# Bottom_PCB_v36.net
KiCad netlist of a schematic drawn in EAGLE
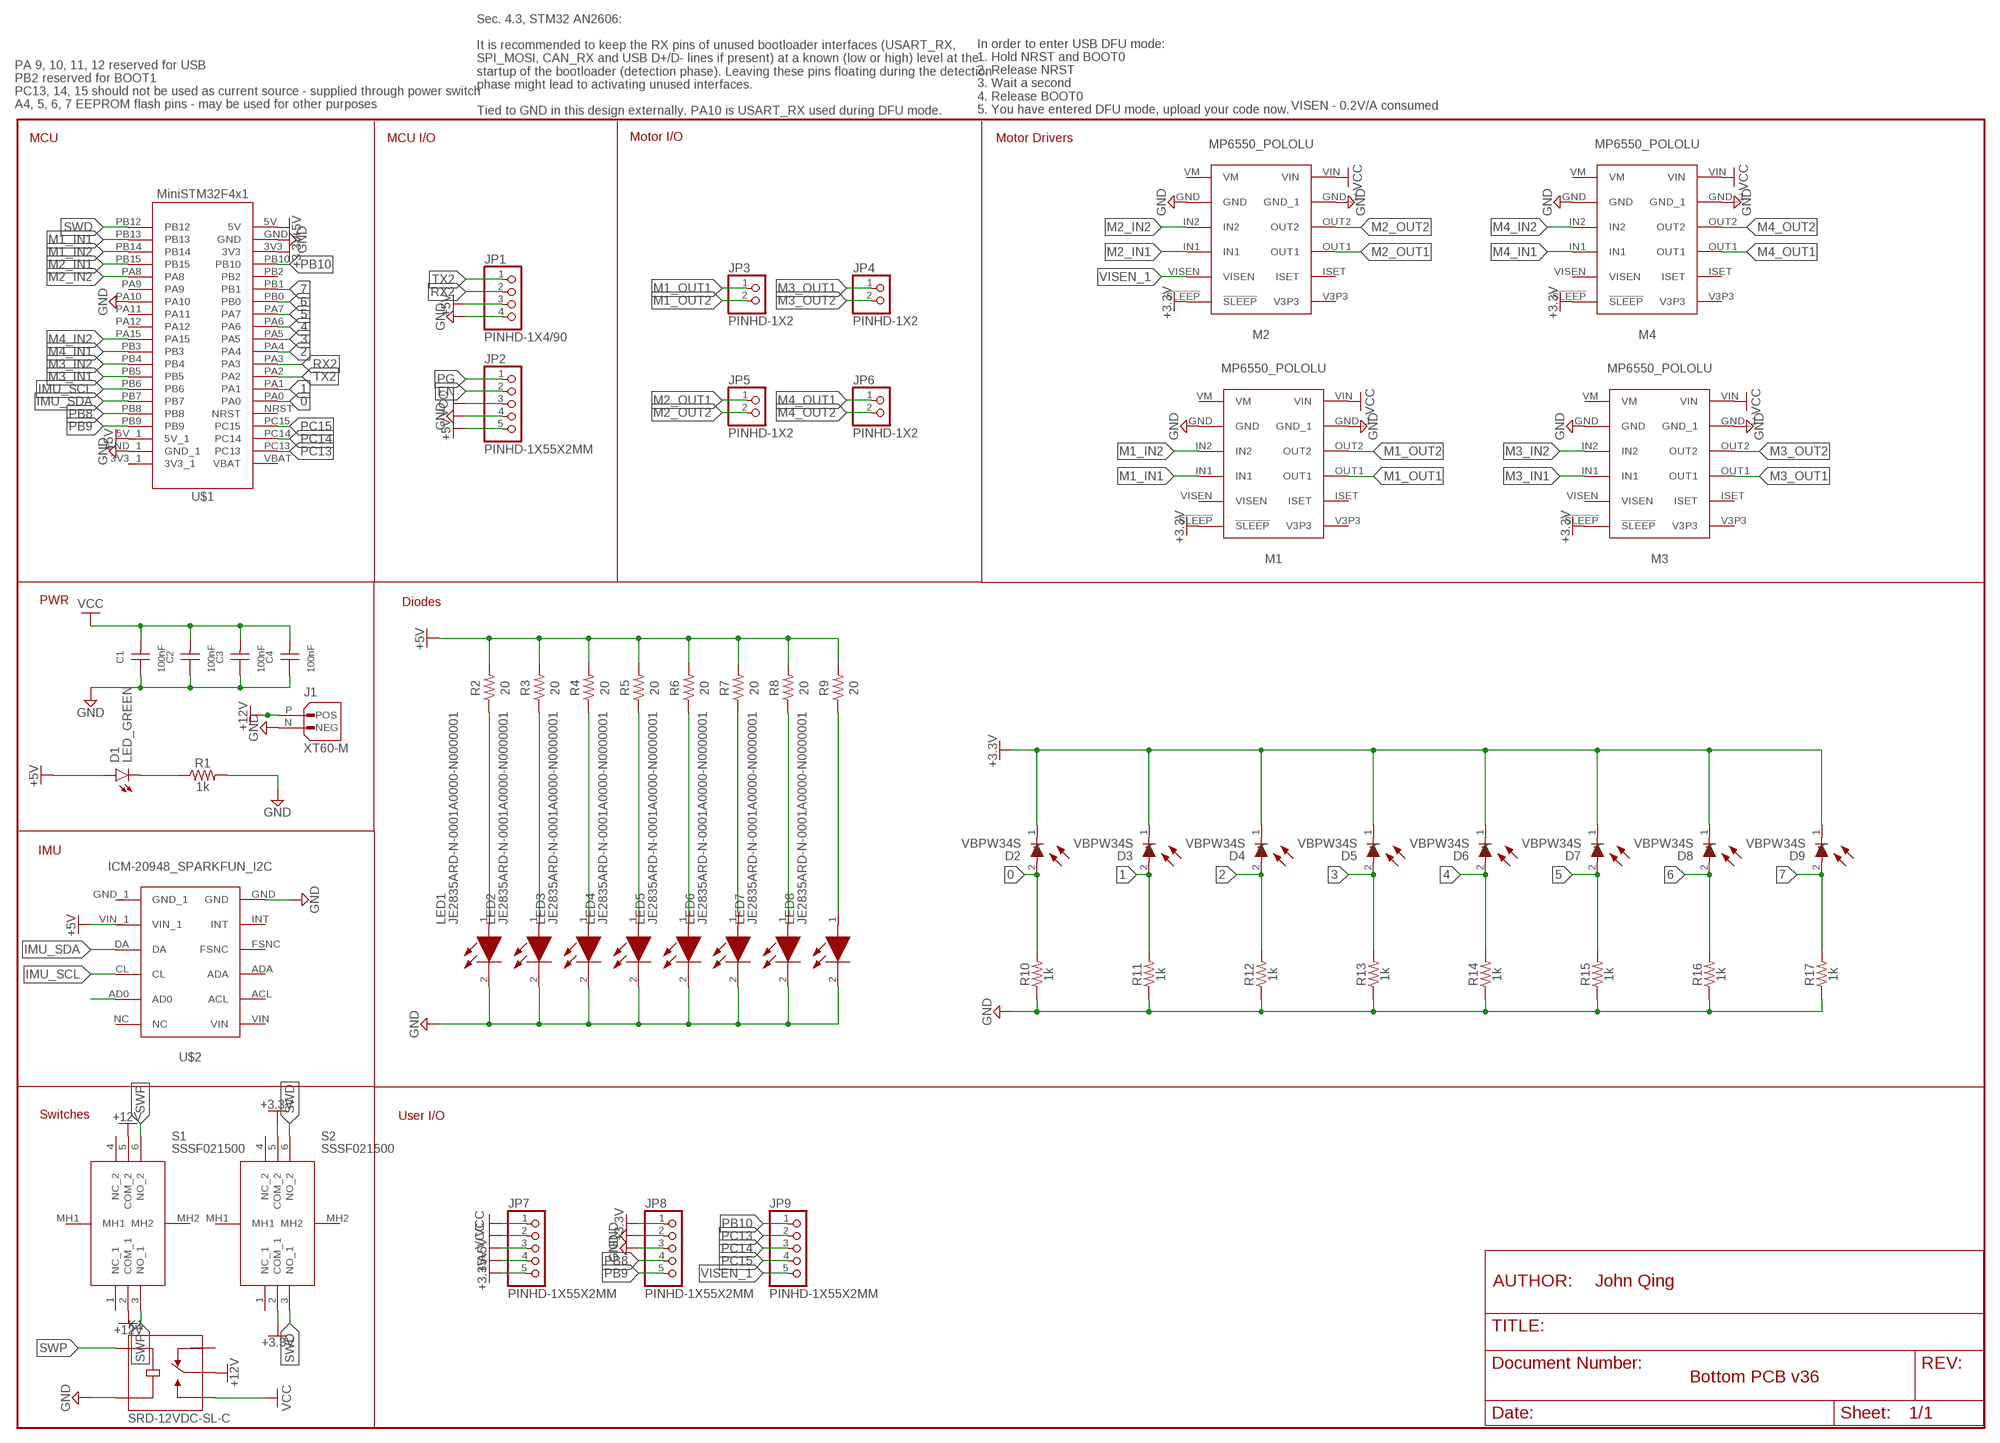
[diagram p0: schematic, sheet 1]

(export (version "E")
  (design (tool "Eeschema 10.0.6"))
  (components
    (comp (ref "C1")
      (value "100nF")
      (footprint "eagle-import:WCAP-CSGP_0603_W")
      (libsource (lib "eagle-import") (part "WCAP-CSGP_0603_100V(DC)_W_885012206120"))
    )
    (comp (ref "C2")
      (value "100nF")
      (footprint "eagle-import:WCAP-CSGP_0603_W")
      (libsource (lib "eagle-import") (part "WCAP-CSGP_0603_100V(DC)_W_885012206120"))
    )
    (comp (ref "C3")
      (value "100nF")
      (footprint "eagle-import:WCAP-CSGP_0603_W")
      (libsource (lib "eagle-import") (part "WCAP-CSGP_0603_100V(DC)_W_885012206120"))
    )
    (comp (ref "C4")
      (value "100nF")
      (footprint "eagle-import:WCAP-CSGP_0603_W")
      (libsource (lib "eagle-import") (part "WCAP-CSGP_0603_100V(DC)_W_885012206120"))
    )
    (comp (ref "D1")
      (value "LED_GREEN")
      (footprint "eagle-import:LEDC1005X25N_FLAT-G")
      (libsource (lib "eagle-import") (part "CHIP-FLAT-G_0402"))
    )
    (comp (ref "D2")
      (value "VBPW34S")
      (footprint "eagle-import:VBPW34S")
      (fields (field (name "MOUSER_PART_NUMBER") "782-VBPW34S"))
      (libsource (lib "eagle-import") (part "VBPW34S"))
    )
    (comp (ref "D3")
      (value "VBPW34S")
      (footprint "eagle-import:VBPW34S")
      (fields (field (name "MOUSER_PART_NUMBER") "782-VBPW34S"))
      (libsource (lib "eagle-import") (part "VBPW34S"))
    )
    (comp (ref "D4")
      (value "VBPW34S")
      (footprint "eagle-import:VBPW34S")
      (fields (field (name "MOUSER_PART_NUMBER") "782-VBPW34S"))
      (libsource (lib "eagle-import") (part "VBPW34S"))
    )
    (comp (ref "D5")
      (value "VBPW34S")
      (footprint "eagle-import:VBPW34S")
      (fields (field (name "MOUSER_PART_NUMBER") "782-VBPW34S"))
      (libsource (lib "eagle-import") (part "VBPW34S"))
    )
    (comp (ref "D6")
      (value "VBPW34S")
      (footprint "eagle-import:VBPW34S")
      (fields (field (name "MOUSER_PART_NUMBER") "782-VBPW34S"))
      (libsource (lib "eagle-import") (part "VBPW34S"))
    )
    (comp (ref "D7")
      (value "VBPW34S")
      (footprint "eagle-import:VBPW34S")
      (fields (field (name "MOUSER_PART_NUMBER") "782-VBPW34S"))
      (libsource (lib "eagle-import") (part "VBPW34S"))
    )
    (comp (ref "D8")
      (value "VBPW34S")
      (footprint "eagle-import:VBPW34S")
      (fields (field (name "MOUSER_PART_NUMBER") "782-VBPW34S"))
      (libsource (lib "eagle-import") (part "VBPW34S"))
    )
    (comp (ref "D9")
      (value "VBPW34S")
      (footprint "eagle-import:VBPW34S")
      (fields (field (name "MOUSER_PART_NUMBER") "782-VBPW34S"))
      (libsource (lib "eagle-import") (part "VBPW34S"))
    )
    (comp (ref "J1")
      (value "XT60-M")
      (footprint "eagle-import:AMASS_XT60-M")
      (fields (field (name "MF") "AMASS"))
      (libsource (lib "eagle-import") (part "XT60-M"))
    )
    (comp (ref "JP1")
      (value "PINHD-1X4/90")
      (footprint "eagle-import:1X04_90")
      (fields (field (name "MANUFACTURER") "Generic"))
      (libsource (lib "eagle-import") (part "PINHD-1X4/90"))
    )
    (comp (ref "JP2")
      (value "PINHD-1X55X2MM")
      (footprint "eagle-import:1_05X2MM")
      (fields (field (name "MANUFACTURER") "Generic"))
      (libsource (lib "eagle-import") (part "PINHD-1X55X2MM"))
    )
    (comp (ref "JP3")
      (value "PINHD-1X2")
      (footprint "eagle-import:1X02")
      (fields (field (name "MANUFACTURER") "Generic"))
      (libsource (lib "eagle-import") (part "PINHD-1X2"))
    )
    (comp (ref "JP4")
      (value "PINHD-1X2")
      (footprint "eagle-import:1X02")
      (fields (field (name "MANUFACTURER") "Generic"))
      (libsource (lib "eagle-import") (part "PINHD-1X2"))
    )
    (comp (ref "JP5")
      (value "PINHD-1X2")
      (footprint "eagle-import:1X02")
      (fields (field (name "MANUFACTURER") "Generic"))
      (libsource (lib "eagle-import") (part "PINHD-1X2"))
    )
    (comp (ref "JP6")
      (value "PINHD-1X2")
      (footprint "eagle-import:1X02")
      (fields (field (name "MANUFACTURER") "Generic"))
      (libsource (lib "eagle-import") (part "PINHD-1X2"))
    )
    (comp (ref "JP7")
      (value "PINHD-1X55X2MM")
      (footprint "eagle-import:1_05X2MM")
      (fields (field (name "MANUFACTURER") "Generic"))
      (libsource (lib "eagle-import") (part "PINHD-1X55X2MM"))
    )
    (comp (ref "JP8")
      (value "PINHD-1X55X2MM")
      (footprint "eagle-import:1_05X2MM")
      (fields (field (name "MANUFACTURER") "Generic"))
      (libsource (lib "eagle-import") (part "PINHD-1X55X2MM"))
    )
    (comp (ref "JP9")
      (value "PINHD-1X55X2MM")
      (footprint "eagle-import:1_05X2MM")
      (fields (field (name "MANUFACTURER") "Generic"))
      (libsource (lib "eagle-import") (part "PINHD-1X55X2MM"))
    )
    (comp (ref "K1")
      (value "SRD-12VDC-SL-C")
      (footprint "eagle-import:RELAY_SRD-12VDC-SL-C")
      (fields (field (name "MF") "Songle Relay"))
      (libsource (lib "eagle-import") (part "SRD-12VDC-SL-C"))
    )
    (comp (ref "LED1")
      (value "JE2835ARD-N-0001A0000-N0000001")
      (footprint "eagle-import:JE2835ARDN0001A0000N0000001")
      (fields (field (name "MOUSER_PART_NUMBER") "941-JE2835ARDN01AN"))
      (libsource (lib "eagle-import") (part "JE2835ARD-N-0001A0000-N0000001"))
    )
    (comp (ref "LED2")
      (value "JE2835ARD-N-0001A0000-N0000001")
      (footprint "eagle-import:JE2835ARDN0001A0000N0000001")
      (fields (field (name "MOUSER_PART_NUMBER") "941-JE2835ARDN01AN"))
      (libsource (lib "eagle-import") (part "JE2835ARD-N-0001A0000-N0000001"))
    )
    (comp (ref "LED3")
      (value "JE2835ARD-N-0001A0000-N0000001")
      (footprint "eagle-import:JE2835ARDN0001A0000N0000001")
      (fields (field (name "MOUSER_PART_NUMBER") "941-JE2835ARDN01AN"))
      (libsource (lib "eagle-import") (part "JE2835ARD-N-0001A0000-N0000001"))
    )
    (comp (ref "LED4")
      (value "JE2835ARD-N-0001A0000-N0000001")
      (footprint "eagle-import:JE2835ARDN0001A0000N0000001")
      (fields (field (name "MOUSER_PART_NUMBER") "941-JE2835ARDN01AN"))
      (libsource (lib "eagle-import") (part "JE2835ARD-N-0001A0000-N0000001"))
    )
    (comp (ref "LED5")
      (value "JE2835ARD-N-0001A0000-N0000001")
      (footprint "eagle-import:JE2835ARDN0001A0000N0000001")
      (fields (field (name "MOUSER_PART_NUMBER") "941-JE2835ARDN01AN"))
      (libsource (lib "eagle-import") (part "JE2835ARD-N-0001A0000-N0000001"))
    )
    (comp (ref "LED6")
      (value "JE2835ARD-N-0001A0000-N0000001")
      (footprint "eagle-import:JE2835ARDN0001A0000N0000001")
      (fields (field (name "MOUSER_PART_NUMBER") "941-JE2835ARDN01AN"))
      (libsource (lib "eagle-import") (part "JE2835ARD-N-0001A0000-N0000001"))
    )
    (comp (ref "LED7")
      (value "JE2835ARD-N-0001A0000-N0000001")
      (footprint "eagle-import:JE2835ARDN0001A0000N0000001")
      (fields (field (name "MOUSER_PART_NUMBER") "941-JE2835ARDN01AN"))
      (libsource (lib "eagle-import") (part "JE2835ARD-N-0001A0000-N0000001"))
    )
    (comp (ref "LED8")
      (value "JE2835ARD-N-0001A0000-N0000001")
      (footprint "eagle-import:JE2835ARDN0001A0000N0000001")
      (fields (field (name "MOUSER_PART_NUMBER") "941-JE2835ARDN01AN"))
      (libsource (lib "eagle-import") (part "JE2835ARD-N-0001A0000-N0000001"))
    )
    (comp (ref "M1")
      (value "MP6550_POLOLU")
      (footprint "eagle-import:MP6550_POLOLU")
      (libsource (lib "eagle-import") (part "MP6550_POLOLU"))
    )
    (comp (ref "M2")
      (value "MP6550_POLOLU")
      (footprint "eagle-import:MP6550_POLOLU")
      (libsource (lib "eagle-import") (part "MP6550_POLOLU"))
    )
    (comp (ref "M3")
      (value "MP6550_POLOLU")
      (footprint "eagle-import:MP6550_POLOLU")
      (libsource (lib "eagle-import") (part "MP6550_POLOLU"))
    )
    (comp (ref "M4")
      (value "MP6550_POLOLU")
      (footprint "eagle-import:MP6550_POLOLU")
      (libsource (lib "eagle-import") (part "MP6550_POLOLU"))
    )
    (comp (ref "R1")
      (value "1k")
      (footprint "eagle-import:0603")
      (libsource (lib "eagle-import") (part "1KOHM-0603-1/10W-1%"))
    )
    (comp (ref "R2")
      (value "20")
      (footprint "eagle-import:RESC3224X71")
      (libsource (lib "eagle-import") (part "R-USCHIP-1210(3225-METRIC)_"))
    )
    (comp (ref "R3")
      (value "20")
      (footprint "eagle-import:RESC3224X71")
      (libsource (lib "eagle-import") (part "R-USCHIP-1210(3225-METRIC)_"))
    )
    (comp (ref "R4")
      (value "20")
      (footprint "eagle-import:RESC3224X71")
      (libsource (lib "eagle-import") (part "R-USCHIP-1210(3225-METRIC)_"))
    )
    (comp (ref "R5")
      (value "20")
      (footprint "eagle-import:RESC3224X71")
      (libsource (lib "eagle-import") (part "R-USCHIP-1210(3225-METRIC)_"))
    )
    (comp (ref "R6")
      (value "20")
      (footprint "eagle-import:RESC3224X71")
      (libsource (lib "eagle-import") (part "R-USCHIP-1210(3225-METRIC)_"))
    )
    (comp (ref "R7")
      (value "20")
      (footprint "eagle-import:RESC3224X71")
      (libsource (lib "eagle-import") (part "R-USCHIP-1210(3225-METRIC)_"))
    )
    (comp (ref "R8")
      (value "20")
      (footprint "eagle-import:RESC3224X71")
      (libsource (lib "eagle-import") (part "R-USCHIP-1210(3225-METRIC)_"))
    )
    (comp (ref "R9")
      (value "20")
      (footprint "eagle-import:RESC3224X71")
      (libsource (lib "eagle-import") (part "R-USCHIP-1210(3225-METRIC)_"))
    )
    (comp (ref "R10")
      (value "1k")
      (footprint "eagle-import:0603")
      (libsource (lib "eagle-import") (part "1KOHM-0603-1/10W-1%"))
    )
    (comp (ref "R11")
      (value "1k")
      (footprint "eagle-import:0603")
      (libsource (lib "eagle-import") (part "1KOHM-0603-1/10W-1%"))
    )
    (comp (ref "R12")
      (value "1k")
      (footprint "eagle-import:0603")
      (libsource (lib "eagle-import") (part "1KOHM-0603-1/10W-1%"))
    )
    (comp (ref "R13")
      (value "1k")
      (footprint "eagle-import:0603")
      (libsource (lib "eagle-import") (part "1KOHM-0603-1/10W-1%"))
    )
    (comp (ref "R14")
      (value "1k")
      (footprint "eagle-import:0603")
      (libsource (lib "eagle-import") (part "1KOHM-0603-1/10W-1%"))
    )
    (comp (ref "R15")
      (value "1k")
      (footprint "eagle-import:0603")
      (libsource (lib "eagle-import") (part "1KOHM-0603-1/10W-1%"))
    )
    (comp (ref "R16")
      (value "1k")
      (footprint "eagle-import:0603")
      (libsource (lib "eagle-import") (part "1KOHM-0603-1/10W-1%"))
    )
    (comp (ref "R17")
      (value "1k")
      (footprint "eagle-import:0603")
      (libsource (lib "eagle-import") (part "1KOHM-0603-1/10W-1%"))
    )
    (comp (ref "S1")
      (value "SSSF021500")
      (footprint "eagle-import:SSSF021500")
      (fields (field (name "MOUSER_PART_NUMBER") "688-SSSF021500"))
      (libsource (lib "eagle-import") (part "SSSF021500"))
    )
    (comp (ref "S2")
      (value "SSSF021500")
      (footprint "eagle-import:SSSF021500")
      (fields (field (name "MOUSER_PART_NUMBER") "688-SSSF021500"))
      (libsource (lib "eagle-import") (part "SSSF021500"))
    )
    (comp (ref "U$1")
      (value "MINISTM32F4X1")
      (footprint "eagle-import:MINISTM32F4X1")
      (libsource (lib "eagle-import") (part "MINISTM32F4X1"))
    )
    (comp (ref "U$2")
      (value "ICM-20948_SPARKFUN_I2C")
      (footprint "eagle-import:ICM-20948_SPARKFUN_I2C")
      (libsource (lib "eagle-import") (part "ICM-20948_SPARKFUN_I2C"))
    )
  )
  (nets
    (net (code "1") (name "+3.3V") (class "Default")
      (node (ref "D2") (pin "1") (pinfunction "K_1") (pintype "bidirectional"))
      (node (ref "D3") (pin "1") (pinfunction "K_1") (pintype "bidirectional"))
      (node (ref "D4") (pin "1") (pinfunction "K_1") (pintype "bidirectional"))
      (node (ref "D5") (pin "1") (pinfunction "K_1") (pintype "bidirectional"))
      (node (ref "D6") (pin "1") (pinfunction "K_1") (pintype "bidirectional"))
      (node (ref "D7") (pin "1") (pinfunction "K_1") (pintype "bidirectional"))
      (node (ref "D8") (pin "1") (pinfunction "K_1") (pintype "bidirectional"))
      (node (ref "D9") (pin "1") (pinfunction "K_1") (pintype "bidirectional"))
      (node (ref "JP7") (pin "5") (pinfunction "5_5") (pintype "passive"))
      (node (ref "JP8") (pin "1") (pinfunction "1_1") (pintype "passive"))
      (node (ref "M1") (pin "!SLEEP") (pinfunction "~{SLEEP}_!SLEEP") (pintype "bidirectional"))
      (node (ref "M2") (pin "!SLEEP") (pinfunction "~{SLEEP}_!SLEEP") (pintype "bidirectional"))
      (node (ref "M3") (pin "!SLEEP") (pinfunction "~{SLEEP}_!SLEEP") (pintype "bidirectional"))
      (node (ref "M4") (pin "!SLEEP") (pinfunction "~{SLEEP}_!SLEEP") (pintype "bidirectional"))
      (node (ref "S2") (pin "2") (pinfunction "COM_1_2") (pintype "bidirectional"))
      (node (ref "S2") (pin "5") (pinfunction "COM_2_5") (pintype "bidirectional"))
      (node (ref "U$1") (pin "3V3") (pinfunction "3V3_3V3") (pintype "power_in"))
    )
    (net (code "2") (name "+5V") (class "Default")
      (node (ref "D1") (pin "A") (pinfunction "A_A") (pintype "passive"))
      (node (ref "JP1") (pin "3") (pinfunction "3_3") (pintype "passive"))
      (node (ref "JP2") (pin "5") (pinfunction "5_5") (pintype "passive"))
      (node (ref "JP7") (pin "3") (pinfunction "3_3") (pintype "passive"))
      (node (ref "JP7") (pin "4") (pinfunction "4_4") (pintype "passive"))
      (node (ref "R2") (pin "2") (pinfunction "2_2") (pintype "passive"))
      (node (ref "R3") (pin "2") (pinfunction "2_2") (pintype "passive"))
      (node (ref "R4") (pin "2") (pinfunction "2_2") (pintype "passive"))
      (node (ref "R5") (pin "2") (pinfunction "2_2") (pintype "passive"))
      (node (ref "R6") (pin "2") (pinfunction "2_2") (pintype "passive"))
      (node (ref "R7") (pin "2") (pinfunction "2_2") (pintype "passive"))
      (node (ref "R8") (pin "2") (pinfunction "2_2") (pintype "passive"))
      (node (ref "R9") (pin "2") (pinfunction "2_2") (pintype "passive"))
      (node (ref "U$1") (pin "5V") (pinfunction "5V_5V") (pintype "power_in"))
      (node (ref "U$1") (pin "5V_1") (pinfunction "5V_1_5V_1") (pintype "power_in"))
      (node (ref "U$2") (pin "VIN_1") (pinfunction "VIN_1_VIN_1") (pintype "bidirectional"))
    )
    (net (code "3") (name "+12V") (class "Default")
      (node (ref "J1") (pin "P") (pinfunction "POS_P") (pintype "passive"))
      (node (ref "K1") (pin "COM") (pinfunction "COM_COM") (pintype "passive"))
      (node (ref "S1") (pin "2") (pinfunction "COM_1_2") (pintype "bidirectional"))
      (node (ref "S1") (pin "5") (pinfunction "COM_2_5") (pintype "bidirectional"))
    )
    (net (code "4") (name "/3V3_1") (class "Default")
      (node (ref "U$1") (pin "3V3_1") (pinfunction "3V3_1_3V3_1") (pintype "power_in"))
    )
    (net (code "5") (name "0") (class "Default")
      (node (ref "D2") (pin "2") (pinfunction "A_2") (pintype "bidirectional"))
      (node (ref "R10") (pin "2") (pinfunction "2_2") (pintype "passive"))
      (node (ref "U$1") (pin "PA0") (pinfunction "PA0_PA0") (pintype "bidirectional"))
    )
    (net (code "6") (name "1") (class "Default")
      (node (ref "D3") (pin "2") (pinfunction "A_2") (pintype "bidirectional"))
      (node (ref "R11") (pin "2") (pinfunction "2_2") (pintype "passive"))
      (node (ref "U$1") (pin "PA1") (pinfunction "PA1_PA1") (pintype "bidirectional"))
    )
    (net (code "7") (name "2") (class "Default")
      (node (ref "D4") (pin "2") (pinfunction "A_2") (pintype "bidirectional"))
      (node (ref "R12") (pin "2") (pinfunction "2_2") (pintype "passive"))
      (node (ref "U$1") (pin "PA4") (pinfunction "PA4_PA4") (pintype "bidirectional"))
    )
    (net (code "8") (name "3") (class "Default")
      (node (ref "D5") (pin "2") (pinfunction "A_2") (pintype "bidirectional"))
      (node (ref "R13") (pin "2") (pinfunction "2_2") (pintype "passive"))
      (node (ref "U$1") (pin "PA5") (pinfunction "PA5_PA5") (pintype "bidirectional"))
    )
    (net (code "9") (name "4") (class "Default")
      (node (ref "D6") (pin "2") (pinfunction "A_2") (pintype "bidirectional"))
      (node (ref "R14") (pin "2") (pinfunction "2_2") (pintype "passive"))
      (node (ref "U$1") (pin "PA6") (pinfunction "PA6_PA6") (pintype "bidirectional"))
    )
    (net (code "10") (name "5") (class "Default")
      (node (ref "D7") (pin "2") (pinfunction "A_2") (pintype "bidirectional"))
      (node (ref "R15") (pin "2") (pinfunction "2_2") (pintype "passive"))
      (node (ref "U$1") (pin "PA7") (pinfunction "PA7_PA7") (pintype "bidirectional"))
    )
    (net (code "11") (name "6") (class "Default")
      (node (ref "D8") (pin "2") (pinfunction "A_2") (pintype "bidirectional"))
      (node (ref "R16") (pin "2") (pinfunction "2_2") (pintype "passive"))
      (node (ref "U$1") (pin "PB0") (pinfunction "PB0_PB0") (pintype "bidirectional"))
    )
    (net (code "12") (name "7") (class "Default")
      (node (ref "D9") (pin "2") (pinfunction "A_2") (pintype "bidirectional"))
      (node (ref "R17") (pin "2") (pinfunction "2_2") (pintype "passive"))
      (node (ref "U$1") (pin "PB1") (pinfunction "PB1_PB1") (pintype "bidirectional"))
    )
    (net (code "13") (name "EN") (class "Default")
      (node (ref "JP2") (pin "2") (pinfunction "2_2") (pintype "passive"))
    )
    (net (code "14") (name "GND") (class "Default")
      (node (ref "C1") (pin "1") (pinfunction "1_1") (pintype "passive"))
      (node (ref "C2") (pin "1") (pinfunction "1_1") (pintype "passive"))
      (node (ref "C3") (pin "1") (pinfunction "1_1") (pintype "passive"))
      (node (ref "C4") (pin "1") (pinfunction "1_1") (pintype "passive"))
      (node (ref "J1") (pin "N") (pinfunction "NEG_N") (pintype "passive"))
      (node (ref "JP1") (pin "4") (pinfunction "4_4") (pintype "passive"))
      (node (ref "JP2") (pin "4") (pinfunction "4_4") (pintype "passive"))
      (node (ref "JP8") (pin "2") (pinfunction "2_2") (pintype "passive"))
      (node (ref "JP8") (pin "3") (pinfunction "3_3") (pintype "passive"))
      (node (ref "K1") (pin "COIL2") (pinfunction "COIL2_COIL2") (pintype "passive"))
      (node (ref "LED1") (pin "2") (pinfunction "K_2") (pintype "bidirectional"))
      (node (ref "LED2") (pin "2") (pinfunction "K_2") (pintype "bidirectional"))
      (node (ref "LED3") (pin "2") (pinfunction "K_2") (pintype "bidirectional"))
      (node (ref "LED4") (pin "2") (pinfunction "K_2") (pintype "bidirectional"))
      (node (ref "LED5") (pin "2") (pinfunction "K_2") (pintype "bidirectional"))
      (node (ref "LED6") (pin "2") (pinfunction "K_2") (pintype "bidirectional"))
      (node (ref "LED7") (pin "2") (pinfunction "K_2") (pintype "bidirectional"))
      (node (ref "LED8") (pin "2") (pinfunction "K_2") (pintype "bidirectional"))
      (node (ref "M1") (pin "GND") (pinfunction "GND_GND") (pintype "bidirectional"))
      (node (ref "M1") (pin "GND_1") (pinfunction "GND_1_GND_1") (pintype "bidirectional"))
      (node (ref "M2") (pin "GND") (pinfunction "GND_GND") (pintype "bidirectional"))
      (node (ref "M2") (pin "GND_1") (pinfunction "GND_1_GND_1") (pintype "bidirectional"))
      (node (ref "M3") (pin "GND") (pinfunction "GND_GND") (pintype "bidirectional"))
      (node (ref "M3") (pin "GND_1") (pinfunction "GND_1_GND_1") (pintype "bidirectional"))
      (node (ref "M4") (pin "GND") (pinfunction "GND_GND") (pintype "bidirectional"))
      (node (ref "M4") (pin "GND_1") (pinfunction "GND_1_GND_1") (pintype "bidirectional"))
      (node (ref "R1") (pin "2") (pinfunction "2_2") (pintype "passive"))
      (node (ref "R10") (pin "1") (pinfunction "1_1") (pintype "passive"))
      (node (ref "R11") (pin "1") (pinfunction "1_1") (pintype "passive"))
      (node (ref "R12") (pin "1") (pinfunction "1_1") (pintype "passive"))
      (node (ref "R13") (pin "1") (pinfunction "1_1") (pintype "passive"))
      (node (ref "R14") (pin "1") (pinfunction "1_1") (pintype "passive"))
      (node (ref "R15") (pin "1") (pinfunction "1_1") (pintype "passive"))
      (node (ref "R16") (pin "1") (pinfunction "1_1") (pintype "passive"))
      (node (ref "R17") (pin "1") (pinfunction "1_1") (pintype "passive"))
      (node (ref "U$1") (pin "GND") (pinfunction "GND_GND") (pintype "power_in"))
      (node (ref "U$1") (pin "GND_1") (pinfunction "GND_1_GND_1") (pintype "power_in"))
      (node (ref "U$1") (pin "PA10") (pinfunction "PA10_PA10") (pintype "bidirectional"))
      (node (ref "U$2") (pin "GND") (pinfunction "GND_GND") (pintype "bidirectional"))
    )
    (net (code "15") (name "IMU_SCL") (class "Default")
      (node (ref "U$1") (pin "PB6") (pinfunction "PB6_PB6") (pintype "bidirectional"))
      (node (ref "U$2") (pin "CL") (pinfunction "CL_CL") (pintype "bidirectional"))
    )
    (net (code "16") (name "IMU_SDA") (class "Default")
      (node (ref "U$1") (pin "PB7") (pinfunction "PB7_PB7") (pintype "bidirectional"))
      (node (ref "U$2") (pin "DA") (pinfunction "DA_DA") (pintype "bidirectional"))
    )
    (net (code "17") (name "M1_IN1") (class "Default")
      (node (ref "M1") (pin "IN1") (pinfunction "IN1_IN1") (pintype "bidirectional"))
      (node (ref "U$1") (pin "PB13") (pinfunction "PB13_PB13") (pintype "bidirectional"))
    )
    (net (code "18") (name "M1_IN2") (class "Default")
      (node (ref "M1") (pin "IN2") (pinfunction "IN2_IN2") (pintype "bidirectional"))
      (node (ref "U$1") (pin "PB14") (pinfunction "PB14_PB14") (pintype "bidirectional"))
    )
    (net (code "19") (name "M1_OUT1") (class "Default")
      (node (ref "JP3") (pin "1") (pinfunction "1_1") (pintype "passive"))
      (node (ref "M1") (pin "OUT1") (pinfunction "OUT1_OUT1") (pintype "bidirectional"))
    )
    (net (code "20") (name "M1_OUT2") (class "Default")
      (node (ref "JP3") (pin "2") (pinfunction "2_2") (pintype "passive"))
      (node (ref "M1") (pin "OUT2") (pinfunction "OUT2_OUT2") (pintype "bidirectional"))
    )
    (net (code "21") (name "M2_IN1") (class "Default")
      (node (ref "M2") (pin "IN1") (pinfunction "IN1_IN1") (pintype "bidirectional"))
      (node (ref "U$1") (pin "PB15") (pinfunction "PB15_PB15") (pintype "bidirectional"))
    )
    (net (code "22") (name "M2_IN2") (class "Default")
      (node (ref "M2") (pin "IN2") (pinfunction "IN2_IN2") (pintype "bidirectional"))
      (node (ref "U$1") (pin "PA8") (pinfunction "PA8_PA8") (pintype "bidirectional"))
    )
    (net (code "23") (name "M2_OUT1") (class "Default")
      (node (ref "JP5") (pin "1") (pinfunction "1_1") (pintype "passive"))
      (node (ref "M2") (pin "OUT1") (pinfunction "OUT1_OUT1") (pintype "bidirectional"))
    )
    (net (code "24") (name "M2_OUT2") (class "Default")
      (node (ref "JP5") (pin "2") (pinfunction "2_2") (pintype "passive"))
      (node (ref "M2") (pin "OUT2") (pinfunction "OUT2_OUT2") (pintype "bidirectional"))
    )
    (net (code "25") (name "M3_IN1") (class "Default")
      (node (ref "M3") (pin "IN1") (pinfunction "IN1_IN1") (pintype "bidirectional"))
      (node (ref "U$1") (pin "PB5") (pinfunction "PB5_PB5") (pintype "bidirectional"))
    )
    (net (code "26") (name "M3_IN2") (class "Default")
      (node (ref "M3") (pin "IN2") (pinfunction "IN2_IN2") (pintype "bidirectional"))
      (node (ref "U$1") (pin "PB4") (pinfunction "PB4_PB4") (pintype "bidirectional"))
    )
    (net (code "27") (name "M3_OUT1") (class "Default")
      (node (ref "JP4") (pin "1") (pinfunction "1_1") (pintype "passive"))
      (node (ref "M3") (pin "OUT1") (pinfunction "OUT1_OUT1") (pintype "bidirectional"))
    )
    (net (code "28") (name "M3_OUT2") (class "Default")
      (node (ref "JP4") (pin "2") (pinfunction "2_2") (pintype "passive"))
      (node (ref "M3") (pin "OUT2") (pinfunction "OUT2_OUT2") (pintype "bidirectional"))
    )
    (net (code "29") (name "M4_IN1") (class "Default")
      (node (ref "M4") (pin "IN1") (pinfunction "IN1_IN1") (pintype "bidirectional"))
      (node (ref "U$1") (pin "PB3") (pinfunction "PB3_PB3") (pintype "bidirectional"))
    )
    (net (code "30") (name "M4_IN2") (class "Default")
      (node (ref "M4") (pin "IN2") (pinfunction "IN2_IN2") (pintype "bidirectional"))
      (node (ref "U$1") (pin "PA15") (pinfunction "PA15_PA15") (pintype "bidirectional"))
    )
    (net (code "31") (name "M4_OUT1") (class "Default")
      (node (ref "JP6") (pin "1") (pinfunction "1_1") (pintype "passive"))
      (node (ref "M4") (pin "OUT1") (pinfunction "OUT1_OUT1") (pintype "bidirectional"))
    )
    (net (code "32") (name "M4_OUT2") (class "Default")
      (node (ref "JP6") (pin "2") (pinfunction "2_2") (pintype "passive"))
      (node (ref "M4") (pin "OUT2") (pinfunction "OUT2_OUT2") (pintype "bidirectional"))
    )
    (net (code "33") (name "Net-(D1-PadC)") (class "Default")
      (node (ref "D1") (pin "C") (pinfunction "C_C") (pintype "passive"))
      (node (ref "R1") (pin "1") (pinfunction "1_1") (pintype "passive"))
    )
    (net (code "34") (name "Net-(LED1-A)") (class "Default")
      (node (ref "LED1") (pin "1") (pinfunction "A_1") (pintype "bidirectional"))
      (node (ref "R2") (pin "1") (pinfunction "1_1") (pintype "passive"))
    )
    (net (code "35") (name "Net-(LED2-A)") (class "Default")
      (node (ref "LED2") (pin "1") (pinfunction "A_1") (pintype "bidirectional"))
      (node (ref "R3") (pin "1") (pinfunction "1_1") (pintype "passive"))
    )
    (net (code "36") (name "Net-(LED3-A)") (class "Default")
      (node (ref "LED3") (pin "1") (pinfunction "A_1") (pintype "bidirectional"))
      (node (ref "R4") (pin "1") (pinfunction "1_1") (pintype "passive"))
    )
    (net (code "37") (name "Net-(LED4-A)") (class "Default")
      (node (ref "LED4") (pin "1") (pinfunction "A_1") (pintype "bidirectional"))
      (node (ref "R5") (pin "1") (pinfunction "1_1") (pintype "passive"))
    )
    (net (code "38") (name "Net-(LED5-A)") (class "Default")
      (node (ref "LED5") (pin "1") (pinfunction "A_1") (pintype "bidirectional"))
      (node (ref "R6") (pin "1") (pinfunction "1_1") (pintype "passive"))
    )
    (net (code "39") (name "Net-(LED6-A)") (class "Default")
      (node (ref "LED6") (pin "1") (pinfunction "A_1") (pintype "bidirectional"))
      (node (ref "R7") (pin "1") (pinfunction "1_1") (pintype "passive"))
    )
    (net (code "40") (name "Net-(LED7-A)") (class "Default")
      (node (ref "LED7") (pin "1") (pinfunction "A_1") (pintype "bidirectional"))
      (node (ref "R8") (pin "1") (pinfunction "1_1") (pintype "passive"))
    )
    (net (code "41") (name "Net-(LED8-A)") (class "Default")
      (node (ref "LED8") (pin "1") (pinfunction "A_1") (pintype "bidirectional"))
      (node (ref "R9") (pin "1") (pinfunction "1_1") (pintype "passive"))
    )
    (net (code "42") (name "PB8") (class "Default")
      (node (ref "JP8") (pin "4") (pinfunction "4_4") (pintype "passive"))
      (node (ref "U$1") (pin "PB8") (pinfunction "PB8_PB8") (pintype "bidirectional"))
    )
    (net (code "43") (name "PB9") (class "Default")
      (node (ref "JP8") (pin "5") (pinfunction "5_5") (pintype "passive"))
      (node (ref "U$1") (pin "PB9") (pinfunction "PB9_PB9") (pintype "bidirectional"))
    )
    (net (code "44") (name "PB10") (class "Default")
      (node (ref "JP9") (pin "1") (pinfunction "1_1") (pintype "passive"))
      (node (ref "U$1") (pin "PB10") (pinfunction "PB10_PB10") (pintype "bidirectional"))
    )
    (net (code "45") (name "PC13") (class "Default")
      (node (ref "JP9") (pin "2") (pinfunction "2_2") (pintype "passive"))
      (node (ref "U$1") (pin "PC13") (pinfunction "PC13_PC13") (pintype "bidirectional"))
    )
    (net (code "46") (name "PC14") (class "Default")
      (node (ref "JP9") (pin "3") (pinfunction "3_3") (pintype "passive"))
      (node (ref "U$1") (pin "PC14") (pinfunction "PC14_PC14") (pintype "bidirectional"))
    )
    (net (code "47") (name "PC15") (class "Default")
      (node (ref "JP9") (pin "4") (pinfunction "4_4") (pintype "passive"))
      (node (ref "U$1") (pin "PC15") (pinfunction "PC15_PC15") (pintype "bidirectional"))
    )
    (net (code "48") (name "PG") (class "Default")
      (node (ref "JP2") (pin "1") (pinfunction "1_1") (pintype "passive"))
    )
    (net (code "49") (name "RX2") (class "Default")
      (node (ref "JP1") (pin "2") (pinfunction "2_2") (pintype "passive"))
      (node (ref "U$1") (pin "PA3") (pinfunction "PA3_PA3") (pintype "bidirectional"))
    )
    (net (code "50") (name "SWD") (class "Default")
      (node (ref "S2") (pin "3") (pinfunction "NO_1_3") (pintype "bidirectional"))
      (node (ref "S2") (pin "6") (pinfunction "NO_2_6") (pintype "bidirectional"))
      (node (ref "U$1") (pin "PB12") (pinfunction "PB12_PB12") (pintype "bidirectional"))
    )
    (net (code "51") (name "SWP") (class "Default")
      (node (ref "K1") (pin "COIL1") (pinfunction "COIL1_COIL1") (pintype "passive"))
      (node (ref "S1") (pin "3") (pinfunction "NO_1_3") (pintype "bidirectional"))
      (node (ref "S1") (pin "6") (pinfunction "NO_2_6") (pintype "bidirectional"))
    )
    (net (code "52") (name "TX2") (class "Default")
      (node (ref "JP1") (pin "1") (pinfunction "1_1") (pintype "passive"))
      (node (ref "U$1") (pin "PA2") (pinfunction "PA2_PA2") (pintype "bidirectional"))
    )
    (net (code "53") (name "VCC") (class "Default")
      (node (ref "C1") (pin "2") (pinfunction "2_2") (pintype "passive"))
      (node (ref "C2") (pin "2") (pinfunction "2_2") (pintype "passive"))
      (node (ref "C3") (pin "2") (pinfunction "2_2") (pintype "passive"))
      (node (ref "C4") (pin "2") (pinfunction "2_2") (pintype "passive"))
      (node (ref "JP2") (pin "3") (pinfunction "3_3") (pintype "passive"))
      (node (ref "JP7") (pin "1") (pinfunction "1_1") (pintype "passive"))
      (node (ref "JP7") (pin "2") (pinfunction "2_2") (pintype "passive"))
      (node (ref "K1") (pin "NO") (pinfunction "NO_NO") (pintype "passive"))
      (node (ref "M1") (pin "VIN") (pinfunction "VIN_VIN") (pintype "bidirectional"))
      (node (ref "M2") (pin "VIN") (pinfunction "VIN_VIN") (pintype "bidirectional"))
      (node (ref "M3") (pin "VIN") (pinfunction "VIN_VIN") (pintype "bidirectional"))
      (node (ref "M4") (pin "VIN") (pinfunction "VIN_VIN") (pintype "bidirectional"))
    )
    (net (code "54") (name "VISEN_1") (class "Default")
      (node (ref "JP9") (pin "5") (pinfunction "5_5") (pintype "passive"))
      (node (ref "M2") (pin "VISEN") (pinfunction "VISEN_VISEN") (pintype "bidirectional"))
    )
    (net (code "55") (name "unconnected-(K1-PadNC)") (class "Default")
      (node (ref "K1") (pin "NC") (pinfunction "NC_NC") (pintype "passive"))
    )
    (net (code "56") (name "unconnected-(M1-PadISET)") (class "Default")
      (node (ref "M1") (pin "ISET") (pinfunction "ISET_ISET") (pintype "bidirectional"))
    )
    (net (code "57") (name "unconnected-(M1-PadV3P3)") (class "Default")
      (node (ref "M1") (pin "V3P3") (pinfunction "V3P3_V3P3") (pintype "bidirectional"))
    )
    (net (code "58") (name "unconnected-(M1-PadVISEN)") (class "Default")
      (node (ref "M1") (pin "VISEN") (pinfunction "VISEN_VISEN") (pintype "bidirectional"))
    )
    (net (code "59") (name "unconnected-(M1-PadVM)") (class "Default")
      (node (ref "M1") (pin "VM") (pinfunction "VM_VM") (pintype "bidirectional"))
    )
    (net (code "60") (name "unconnected-(M2-PadISET)") (class "Default")
      (node (ref "M2") (pin "ISET") (pinfunction "ISET_ISET") (pintype "bidirectional"))
    )
    (net (code "61") (name "unconnected-(M2-PadV3P3)") (class "Default")
      (node (ref "M2") (pin "V3P3") (pinfunction "V3P3_V3P3") (pintype "bidirectional"))
    )
    (net (code "62") (name "unconnected-(M2-PadVM)") (class "Default")
      (node (ref "M2") (pin "VM") (pinfunction "VM_VM") (pintype "bidirectional"))
    )
    (net (code "63") (name "unconnected-(M3-PadISET)") (class "Default")
      (node (ref "M3") (pin "ISET") (pinfunction "ISET_ISET") (pintype "bidirectional"))
    )
    (net (code "64") (name "unconnected-(M3-PadV3P3)") (class "Default")
      (node (ref "M3") (pin "V3P3") (pinfunction "V3P3_V3P3") (pintype "bidirectional"))
    )
    (net (code "65") (name "unconnected-(M3-PadVISEN)") (class "Default")
      (node (ref "M3") (pin "VISEN") (pinfunction "VISEN_VISEN") (pintype "bidirectional"))
    )
    (net (code "66") (name "unconnected-(M3-PadVM)") (class "Default")
      (node (ref "M3") (pin "VM") (pinfunction "VM_VM") (pintype "bidirectional"))
    )
    (net (code "67") (name "unconnected-(M4-PadISET)") (class "Default")
      (node (ref "M4") (pin "ISET") (pinfunction "ISET_ISET") (pintype "bidirectional"))
    )
    (net (code "68") (name "unconnected-(M4-PadV3P3)") (class "Default")
      (node (ref "M4") (pin "V3P3") (pinfunction "V3P3_V3P3") (pintype "bidirectional"))
    )
    (net (code "69") (name "unconnected-(M4-PadVISEN)") (class "Default")
      (node (ref "M4") (pin "VISEN") (pinfunction "VISEN_VISEN") (pintype "bidirectional"))
    )
    (net (code "70") (name "unconnected-(M4-PadVM)") (class "Default")
      (node (ref "M4") (pin "VM") (pinfunction "VM_VM") (pintype "bidirectional"))
    )
    (net (code "71") (name "unconnected-(S1-NC_1-Pad1)") (class "Default")
      (node (ref "S1") (pin "1") (pinfunction "NC_1_1") (pintype "bidirectional"))
    )
    (net (code "72") (name "unconnected-(S1-NC_2-Pad4)") (class "Default")
      (node (ref "S1") (pin "4") (pinfunction "NC_2_4") (pintype "bidirectional"))
    )
    (net (code "73") (name "unconnected-(S1-PadMH1)") (class "Default")
      (node (ref "S1") (pin "MH1") (pinfunction "MH1_MH1") (pintype "bidirectional"))
    )
    (net (code "74") (name "unconnected-(S1-PadMH2)") (class "Default")
      (node (ref "S1") (pin "MH2") (pinfunction "MH2_MH2") (pintype "bidirectional"))
    )
    (net (code "75") (name "unconnected-(S2-NC_1-Pad1)") (class "Default")
      (node (ref "S2") (pin "1") (pinfunction "NC_1_1") (pintype "bidirectional"))
    )
    (net (code "76") (name "unconnected-(S2-NC_2-Pad4)") (class "Default")
      (node (ref "S2") (pin "4") (pinfunction "NC_2_4") (pintype "bidirectional"))
    )
    (net (code "77") (name "unconnected-(S2-PadMH1)") (class "Default")
      (node (ref "S2") (pin "MH1") (pinfunction "MH1_MH1") (pintype "bidirectional"))
    )
    (net (code "78") (name "unconnected-(S2-PadMH2)") (class "Default")
      (node (ref "S2") (pin "MH2") (pinfunction "MH2_MH2") (pintype "bidirectional"))
    )
    (net (code "79") (name "unconnected-(U$1-PadNRST)") (class "Default")
      (node (ref "U$1") (pin "NRST") (pinfunction "NRST_NRST") (pintype "bidirectional"))
    )
    (net (code "80") (name "unconnected-(U$1-PadPA9)") (class "Default")
      (node (ref "U$1") (pin "PA9") (pinfunction "PA9_PA9") (pintype "bidirectional"))
    )
    (net (code "81") (name "unconnected-(U$1-PadPA11)") (class "Default")
      (node (ref "U$1") (pin "PA11") (pinfunction "PA11_PA11") (pintype "bidirectional"))
    )
    (net (code "82") (name "unconnected-(U$1-PadPA12)") (class "Default")
      (node (ref "U$1") (pin "PA12") (pinfunction "PA12_PA12") (pintype "bidirectional"))
    )
    (net (code "83") (name "unconnected-(U$1-PadPB2)") (class "Default")
      (node (ref "U$1") (pin "PB2") (pinfunction "PB2_PB2") (pintype "bidirectional"))
    )
    (net (code "84") (name "unconnected-(U$1-PadVBAT)") (class "Default")
      (node (ref "U$1") (pin "VBAT") (pinfunction "VBAT_VBAT") (pintype "bidirectional"))
    )
    (net (code "85") (name "unconnected-(U$2-PadACL)") (class "Default")
      (node (ref "U$2") (pin "ACL") (pinfunction "ACL_ACL") (pintype "bidirectional"))
    )
    (net (code "86") (name "unconnected-(U$2-PadAD0)") (class "Default")
      (node (ref "U$2") (pin "AD0") (pinfunction "AD0_AD0") (pintype "bidirectional"))
    )
    (net (code "87") (name "unconnected-(U$2-PadADA)") (class "Default")
      (node (ref "U$2") (pin "ADA") (pinfunction "ADA_ADA") (pintype "bidirectional"))
    )
    (net (code "88") (name "unconnected-(U$2-PadFSNC)") (class "Default")
      (node (ref "U$2") (pin "FSNC") (pinfunction "FSNC_FSNC") (pintype "bidirectional"))
    )
    (net (code "89") (name "unconnected-(U$2-PadGND_1)") (class "Default")
      (node (ref "U$2") (pin "GND_1") (pinfunction "GND_1_GND_1") (pintype "bidirectional"))
    )
    (net (code "90") (name "unconnected-(U$2-PadINT)") (class "Default")
      (node (ref "U$2") (pin "INT") (pinfunction "INT_INT") (pintype "bidirectional"))
    )
    (net (code "91") (name "unconnected-(U$2-PadNC)") (class "Default")
      (node (ref "U$2") (pin "NC") (pinfunction "NC_NC") (pintype "bidirectional"))
    )
    (net (code "92") (name "unconnected-(U$2-PadVIN)") (class "Default")
      (node (ref "U$2") (pin "VIN") (pinfunction "VIN_VIN") (pintype "bidirectional"))
    )
  )
)
